# Analog_Light_Project_Improved_Schematic.net
KiCad netlist of a schematic drawn in EAGLE
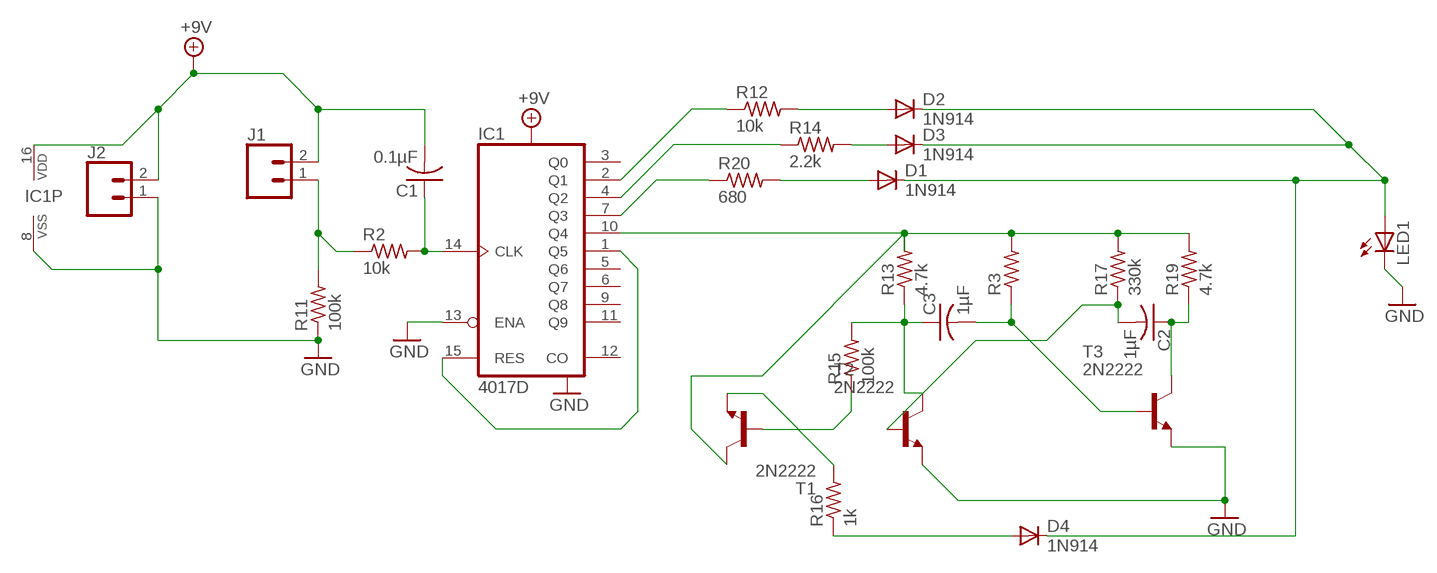
[diagram p0: schematic, sheet 1]

(export (version "E")
  (design (tool "Eeschema 10.0.6"))
  (components
    (comp (ref "C1")
      (value "0.1µF")
      (footprint "eagle-import:C025-024X044")
      (libsource (lib "eagle-import") (part "rcl_334_C-US025-024X044"))
    )
    (comp (ref "C2")
      (value "1µF")
      (footprint "eagle-import:C0805")
      (libsource (lib "eagle-import") (part "C-USC0805"))
    )
    (comp (ref "C3")
      (value "1µF")
      (footprint "eagle-import:C025-024X044")
      (libsource (lib "eagle-import") (part "rcl_334_C-US025-024X044"))
    )
    (comp (ref "D1")
      (value "1N914")
      (footprint "eagle-import:DO41-10")
      (libsource (lib "eagle-import") (part "1N4004"))
    )
    (comp (ref "D2")
      (value "1N914")
      (footprint "eagle-import:DO41-10")
      (libsource (lib "eagle-import") (part "1N4004"))
    )
    (comp (ref "D3")
      (value "1N914")
      (footprint "eagle-import:DO41-10")
      (libsource (lib "eagle-import") (part "1N4004"))
    )
    (comp (ref "D4")
      (value "1N914")
      (footprint "eagle-import:DO41-10")
      (libsource (lib "eagle-import") (part "1N4004"))
    )
    (comp (ref "IC1")
      (value "4017D")
      (footprint "eagle-import:SO16")
      (libsource (lib "eagle-import") (part "4017D"))
    )
    (comp (ref "J1")
      (value "CONN_02")
      (footprint "eagle-import:1X02")
      (libsource (lib "eagle-import") (part "CONN_02"))
    )
    (comp (ref "J2")
      (value "CONN_02")
      (footprint "eagle-import:1X02")
      (libsource (lib "eagle-import") (part "CONN_02"))
    )
    (comp (ref "LED1")
      (value "LED5MM")
      (footprint "eagle-import:LED5MM")
      (libsource (lib "eagle-import") (part "LED5MM"))
    )
    (comp (ref "R2")
      (value "10k")
      (footprint "eagle-import:0204_5")
      (libsource (lib "eagle-import") (part "rcl_334_R-US_0204/5"))
    )
    (comp (ref "R3")
      (value "R-US_0204/5")
      (footprint "eagle-import:0204_5")
      (libsource (lib "eagle-import") (part "rcl_334_R-US_0204/5"))
    )
    (comp (ref "R11")
      (value "100k")
      (footprint "eagle-import:M0805")
      (libsource (lib "eagle-import") (part "R-US_M0805"))
    )
    (comp (ref "R12")
      (value "10k")
      (footprint "eagle-import:M0805")
      (libsource (lib "eagle-import") (part "R-US_M0805"))
    )
    (comp (ref "R13")
      (value "4.7k")
      (footprint "eagle-import:M0805")
      (libsource (lib "eagle-import") (part "R-US_M0805"))
    )
    (comp (ref "R14")
      (value "2.2k")
      (footprint "eagle-import:M0805")
      (libsource (lib "eagle-import") (part "R-US_M0805"))
    )
    (comp (ref "R15")
      (value "100k")
      (footprint "eagle-import:M0805")
      (libsource (lib "eagle-import") (part "R-US_M0805"))
    )
    (comp (ref "R16")
      (value "1k")
      (footprint "eagle-import:M0805")
      (libsource (lib "eagle-import") (part "R-US_M0805"))
    )
    (comp (ref "R17")
      (value "330k")
      (footprint "eagle-import:M0805")
      (libsource (lib "eagle-import") (part "R-US_M0805"))
    )
    (comp (ref "R19")
      (value "4.7k")
      (footprint "eagle-import:M0805")
      (libsource (lib "eagle-import") (part "R-US_M0805"))
    )
    (comp (ref "R20")
      (value "680")
      (footprint "eagle-import:M0805")
      (libsource (lib "eagle-import") (part "R-US_M0805"))
    )
    (comp (ref "T1")
      (value "2N2222")
      (footprint "eagle-import:TO92-EBC-OVAL")
      (libsource (lib "eagle-import") (part "2N2222"))
    )
    (comp (ref "T2")
      (value "2N2222")
      (footprint "eagle-import:TO92-EBC-OVAL")
      (libsource (lib "eagle-import") (part "2N2222"))
    )
    (comp (ref "T3")
      (value "2N2222")
      (footprint "eagle-import:TO92-EBC-OVAL")
      (libsource (lib "eagle-import") (part "2N2222"))
    )
  )
  (nets
    (net (code "1") (name "+9V") (class "Default")
      (node (ref "C1") (pin "2") (pinfunction "2_2") (pintype "passive"))
      (node (ref "IC1") (pin "16") (pinfunction "VDD_16") (pintype "power_in"))
      (node (ref "J1") (pin "2") (pinfunction "2_2") (pintype "passive"))
      (node (ref "J2") (pin "2") (pinfunction "2_2") (pintype "passive"))
    )
    (net (code "2") (name "GND") (class "Default")
      (node (ref "IC1") (pin "13") (pinfunction "ENA_13") (pintype "input"))
      (node (ref "IC1") (pin "8") (pinfunction "VSS_8") (pintype "power_in"))
      (node (ref "J2") (pin "1") (pinfunction "1_1") (pintype "passive"))
      (node (ref "LED1") (pin "K") (pinfunction "C_K") (pintype "passive"))
      (node (ref "R11") (pin "1") (pinfunction "1_1") (pintype "passive"))
      (node (ref "T2") (pin "E") (pinfunction "E_E") (pintype "passive"))
      (node (ref "T3") (pin "E") (pinfunction "E_E") (pintype "passive"))
    )
    (net (code "3") (name "Net-(C2-Pad1)") (class "Default")
      (node (ref "C2") (pin "1") (pinfunction "1_1") (pintype "passive"))
      (node (ref "R19") (pin "1") (pinfunction "1_1") (pintype "passive"))
      (node (ref "T3") (pin "C") (pinfunction "C_C") (pintype "passive"))
    )
    (net (code "4") (name "Net-(C2-Pad2)") (class "Default")
      (node (ref "C2") (pin "2") (pinfunction "2_2") (pintype "passive"))
      (node (ref "R17") (pin "1") (pinfunction "1_1") (pintype "passive"))
      (node (ref "T2") (pin "B") (pinfunction "B_B") (pintype "passive"))
    )
    (net (code "5") (name "Net-(C3-Pad1)") (class "Default")
      (node (ref "C3") (pin "1") (pinfunction "1_1") (pintype "passive"))
      (node (ref "R13") (pin "1") (pinfunction "1_1") (pintype "passive"))
      (node (ref "R15") (pin "2") (pinfunction "2_2") (pintype "passive"))
      (node (ref "T2") (pin "C") (pinfunction "C_C") (pintype "passive"))
    )
    (net (code "6") (name "Net-(C3-Pad2)") (class "Default")
      (node (ref "C3") (pin "2") (pinfunction "2_2") (pintype "passive"))
      (node (ref "R3") (pin "1") (pinfunction "1_1") (pintype "passive"))
      (node (ref "T3") (pin "B") (pinfunction "B_B") (pintype "passive"))
    )
    (net (code "7") (name "Net-(D1-PadA)") (class "Default")
      (node (ref "D1") (pin "A") (pinfunction "A_A") (pintype "passive"))
      (node (ref "R20") (pin "2") (pinfunction "2_2") (pintype "passive"))
    )
    (net (code "8") (name "Net-(D1-PadC)") (class "Default")
      (node (ref "D1") (pin "C") (pinfunction "C_C") (pintype "passive"))
      (node (ref "D2") (pin "C") (pinfunction "C_C") (pintype "passive"))
      (node (ref "D3") (pin "C") (pinfunction "C_C") (pintype "passive"))
      (node (ref "D4") (pin "C") (pinfunction "C_C") (pintype "passive"))
      (node (ref "LED1") (pin "A") (pinfunction "A_A") (pintype "passive"))
    )
    (net (code "9") (name "Net-(D2-PadA)") (class "Default")
      (node (ref "D2") (pin "A") (pinfunction "A_A") (pintype "passive"))
      (node (ref "R12") (pin "2") (pinfunction "2_2") (pintype "passive"))
    )
    (net (code "10") (name "Net-(D3-PadA)") (class "Default")
      (node (ref "D3") (pin "A") (pinfunction "A_A") (pintype "passive"))
      (node (ref "R14") (pin "2") (pinfunction "2_2") (pintype "passive"))
    )
    (net (code "11") (name "Net-(D4-PadA)") (class "Default")
      (node (ref "D4") (pin "A") (pinfunction "A_A") (pintype "passive"))
      (node (ref "R16") (pin "1") (pinfunction "1_1") (pintype "passive"))
    )
    (net (code "12") (name "Net-(IC1A-CLK)") (class "Default")
      (node (ref "C1") (pin "1") (pinfunction "1_1") (pintype "passive"))
      (node (ref "IC1") (pin "14") (pinfunction "CLK_14") (pintype "input"))
      (node (ref "R2") (pin "2") (pinfunction "2_2") (pintype "passive"))
    )
    (net (code "13") (name "Net-(IC1A-Q1)") (class "Default")
      (node (ref "IC1") (pin "2") (pinfunction "Q1_2") (pintype "output"))
      (node (ref "R12") (pin "1") (pinfunction "1_1") (pintype "passive"))
    )
    (net (code "14") (name "Net-(IC1A-Q2)") (class "Default")
      (node (ref "IC1") (pin "4") (pinfunction "Q2_4") (pintype "output"))
      (node (ref "R14") (pin "1") (pinfunction "1_1") (pintype "passive"))
    )
    (net (code "15") (name "Net-(IC1A-Q3)") (class "Default")
      (node (ref "IC1") (pin "7") (pinfunction "Q3_7") (pintype "output"))
      (node (ref "R20") (pin "1") (pinfunction "1_1") (pintype "passive"))
    )
    (net (code "16") (name "Net-(IC1A-Q4)") (class "Default")
      (node (ref "IC1") (pin "10") (pinfunction "Q4_10") (pintype "output"))
      (node (ref "R13") (pin "2") (pinfunction "2_2") (pintype "passive"))
      (node (ref "R17") (pin "2") (pinfunction "2_2") (pintype "passive"))
      (node (ref "R19") (pin "2") (pinfunction "2_2") (pintype "passive"))
      (node (ref "R3") (pin "2") (pinfunction "2_2") (pintype "passive"))
      (node (ref "T1") (pin "C") (pinfunction "C_C") (pintype "passive"))
    )
    (net (code "17") (name "Net-(IC1A-Q5)") (class "Default")
      (node (ref "IC1") (pin "1") (pinfunction "Q5_1") (pintype "output"))
      (node (ref "IC1") (pin "15") (pinfunction "RES_15") (pintype "input"))
    )
    (net (code "18") (name "Net-(J1-Pad1)") (class "Default")
      (node (ref "J1") (pin "1") (pinfunction "1_1") (pintype "passive"))
      (node (ref "R11") (pin "2") (pinfunction "2_2") (pintype "passive"))
      (node (ref "R2") (pin "1") (pinfunction "1_1") (pintype "passive"))
    )
    (net (code "19") (name "Net-(R15-Pad1)") (class "Default")
      (node (ref "R15") (pin "1") (pinfunction "1_1") (pintype "passive"))
      (node (ref "T1") (pin "B") (pinfunction "B_B") (pintype "passive"))
    )
    (net (code "20") (name "Net-(R16-Pad2)") (class "Default")
      (node (ref "R16") (pin "2") (pinfunction "2_2") (pintype "passive"))
      (node (ref "T1") (pin "E") (pinfunction "E_E") (pintype "passive"))
    )
    (net (code "21") (name "unconnected-(IC1A-CO-Pad12)") (class "Default")
      (node (ref "IC1") (pin "12") (pinfunction "CO_12") (pintype "output"))
    )
    (net (code "22") (name "unconnected-(IC1A-Q0-Pad3)") (class "Default")
      (node (ref "IC1") (pin "3") (pinfunction "Q0_3") (pintype "output"))
    )
    (net (code "23") (name "unconnected-(IC1A-Q6-Pad5)") (class "Default")
      (node (ref "IC1") (pin "5") (pinfunction "Q6_5") (pintype "output"))
    )
    (net (code "24") (name "unconnected-(IC1A-Q7-Pad6)") (class "Default")
      (node (ref "IC1") (pin "6") (pinfunction "Q7_6") (pintype "output"))
    )
    (net (code "25") (name "unconnected-(IC1A-Q8-Pad9)") (class "Default")
      (node (ref "IC1") (pin "9") (pinfunction "Q8_9") (pintype "output"))
    )
    (net (code "26") (name "unconnected-(IC1A-Q9-Pad11)") (class "Default")
      (node (ref "IC1") (pin "11") (pinfunction "Q9_11") (pintype "output"))
    )
  )
)
